# Sheet1.net
KiCad netlist of a schematic drawn in Altium Designer
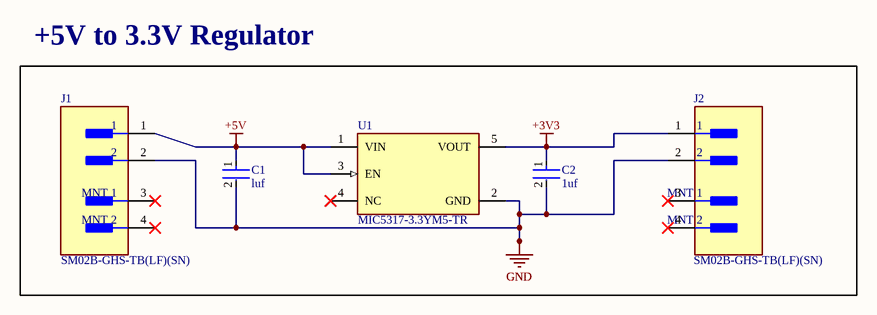
[diagram p0: Sheet1.SchDoc]

(export (version "E")
  (design (tool "Eeschema 10.0.6"))
  (components
    (comp (ref "C1")
      (value "luf")
      (footprint "FP-CC0805-0_85-MFG")
      (description "CC0805 1 uF X7R 10.00% 10 V")
      (fields
        (field (name "OCTOPART") "https://octopart.com/cc0805kfx7r6bb105-yageo-12756113")
        (field (name "MANUFACTURER PART NUMBER") "CC0805KFX7R6BB105")
      )
      (libsource (lib "Altium Content Vault") (part "11868f565c42a9108669ba33697ecf6"))
    )
    (comp (ref "C2")
      (value "1uf")
      (footprint "FP-CC0805-0_85-MFG")
      (description "CC0805 1 uF X7R 10.00% 10 V")
      (fields
        (field (name "OCTOPART") "https://octopart.com/cc0805kfx7r6bb105-yageo-12756113")
        (field (name "MANUFACTURER PART NUMBER") "CC0805KFX7R6BB105")
      )
      (libsource (lib "Altium Content Vault") (part "11868f565c42a9108669ba33697ecf6"))
    )
    (comp (ref "J1")
      (value "SM02B-GHS-TB(LF)(SN)")
      (footprint "FP-SM02B-GHS-TB_LF_SN-MFG")
      (description "CONN HEADER SMD R/A 2POS 1.25MM")
      (libsource (lib "") (part "56ec3178a87b3978bdc1b3682cd516a_1"))
    )
    (comp (ref "J2")
      (value "SM02B-GHS-TB(LF)(SN)")
      (footprint "FP-SM02B-GHS-TB_LF_SN-MFG")
      (description "CONN HEADER SMD R/A 2POS 1.25MM")
      (libsource (lib "Altium Content Vault") (part "56ec3178a87b3978bdc1b3682cd516a"))
    )
    (comp (ref "U1")
      (value "MIC5317-3.3YM5-TR")
      (footprint "FP-SOT23-5LD-PL-1-MFG")
      (description "IC REG LINEAR 3.3V 150MA SOT23-5")
      (libsource (lib "Altium Content Vault") (part "0a093dae7315cdc977fd108dde87457"))
    )
  )
  (nets
    (net (code "1") (name "+3V3") (class "Default")
      (node (ref "C2") (pin "1") (pinfunction "1_1") (pintype "passive"))
      (node (ref "J2") (pin "1") (pinfunction "1_1") (pintype "passive"))
      (node (ref "U1") (pin "5") (pinfunction "VOUT_5") (pintype "power_in"))
    )
    (net (code "2") (name "+5V") (class "Default")
      (node (ref "C1") (pin "1") (pinfunction "1_1") (pintype "passive"))
      (node (ref "J1") (pin "1") (pinfunction "1_1") (pintype "passive"))
      (node (ref "U1") (pin "1") (pinfunction "VIN_1") (pintype "power_in"))
      (node (ref "U1") (pin "3") (pinfunction "EN_3") (pintype "input"))
    )
    (net (code "3") (name "GND") (class "Default")
      (node (ref "C1") (pin "2") (pinfunction "2_2") (pintype "passive"))
      (node (ref "C2") (pin "2") (pinfunction "2_2") (pintype "passive"))
      (node (ref "J1") (pin "2") (pinfunction "2_2") (pintype "passive"))
      (node (ref "J2") (pin "2") (pinfunction "2_2") (pintype "passive"))
      (node (ref "U1") (pin "2") (pinfunction "GND_2") (pintype "power_in"))
    )
    (net (code "4") (name "unconnected-(J1-MNT_1-Pad3)") (class "Default")
      (node (ref "J1") (pin "3") (pinfunction "MNT_1_3") (pintype "passive+no_connect"))
    )
    (net (code "5") (name "unconnected-(J1-MNT_2-Pad4)") (class "Default")
      (node (ref "J1") (pin "4") (pinfunction "MNT_2_4") (pintype "passive+no_connect"))
    )
    (net (code "6") (name "unconnected-(J2-MNT_1-Pad3)") (class "Default")
      (node (ref "J2") (pin "3") (pinfunction "MNT_1_3") (pintype "passive+no_connect"))
    )
    (net (code "7") (name "unconnected-(J2-MNT_2-Pad4)") (class "Default")
      (node (ref "J2") (pin "4") (pinfunction "MNT_2_4") (pintype "passive+no_connect"))
    )
    (net (code "8") (name "unconnected-(U1-NC-Pad4)") (class "Default")
      (node (ref "U1") (pin "4") (pinfunction "NC_4") (pintype "passive+no_connect"))
    )
  )
)
